# LoRa_Mini_Dev_v1_3.net
KiCad netlist of a schematic drawn in EAGLE
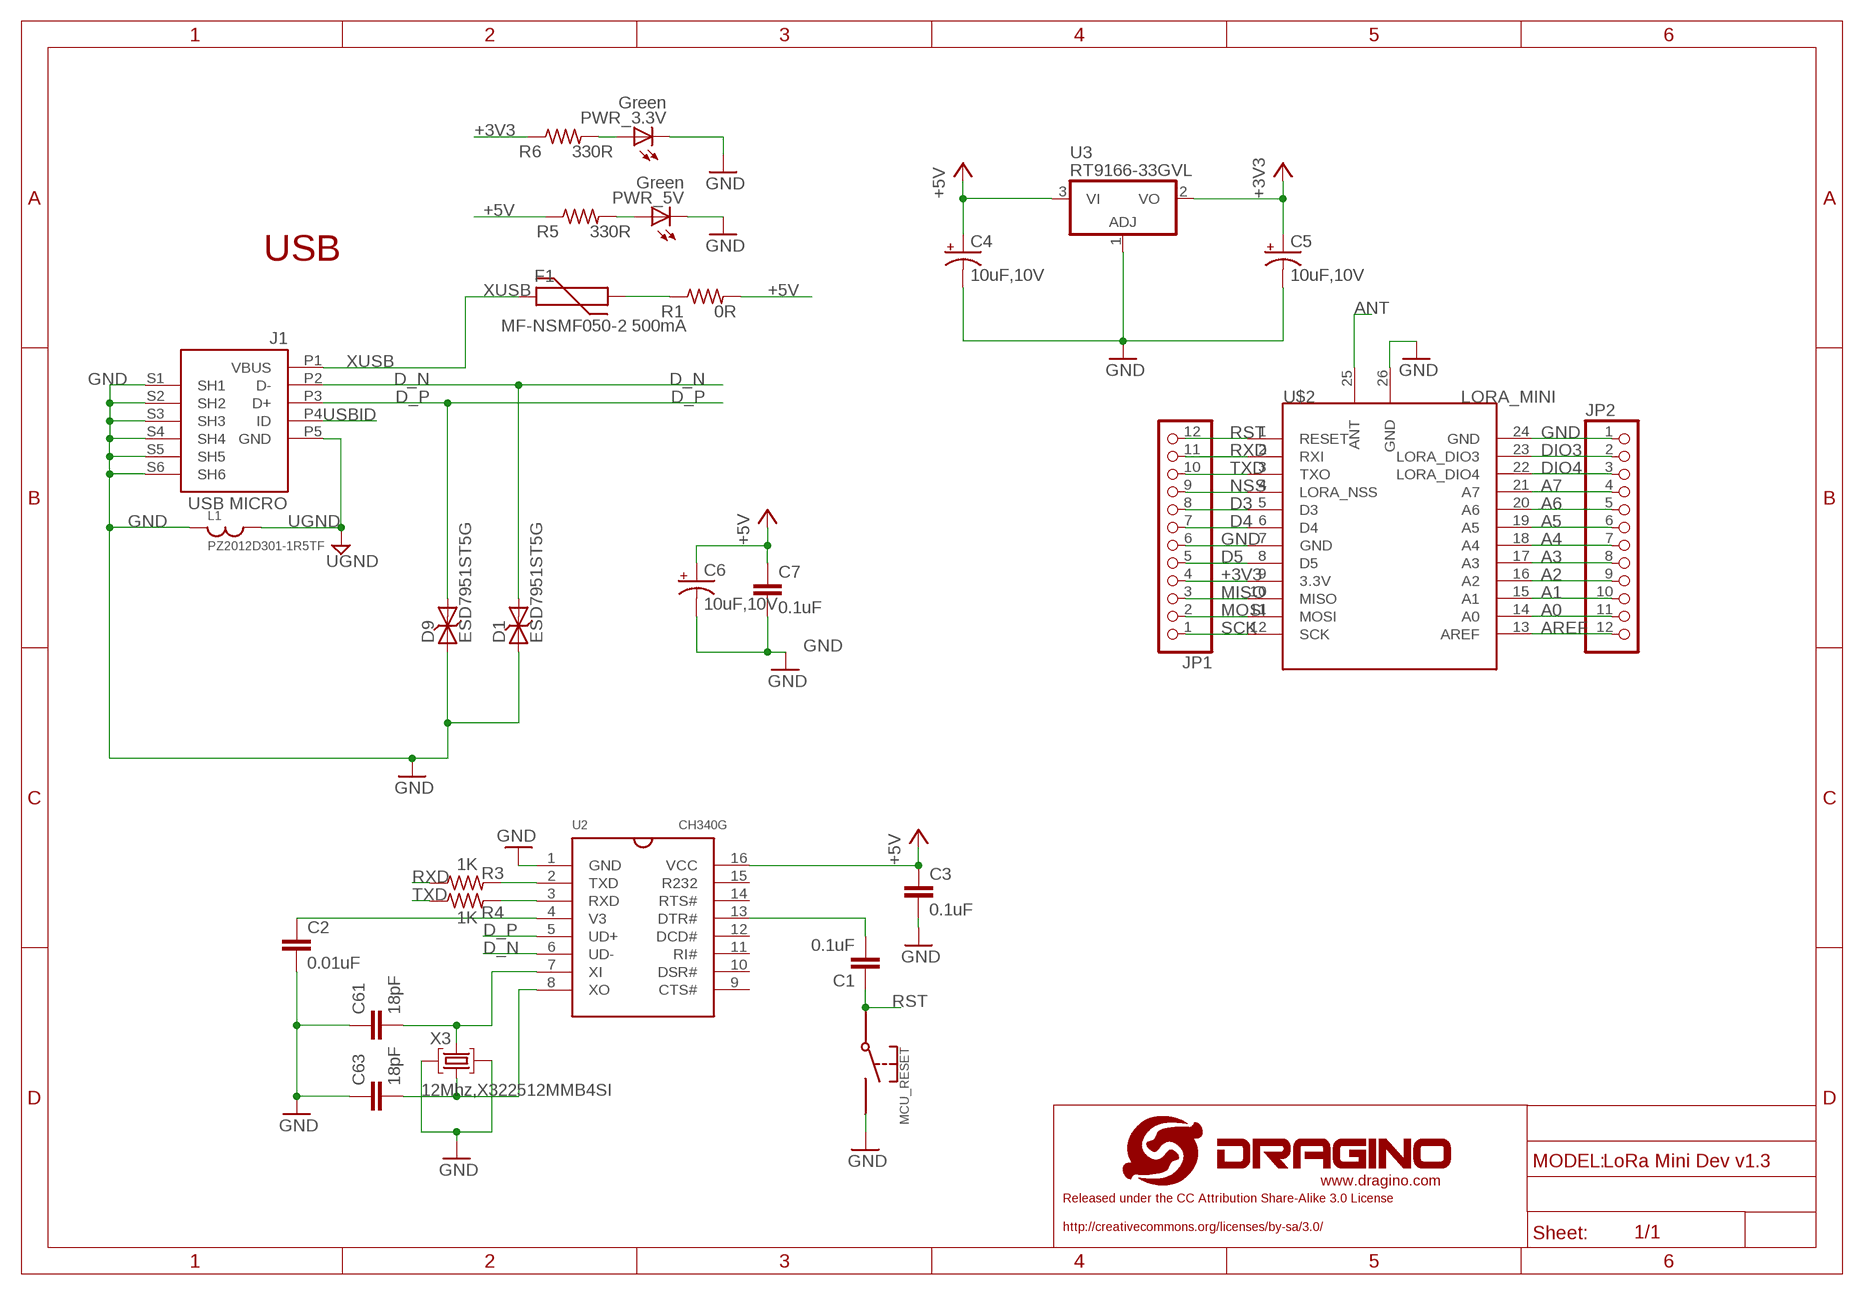
[diagram p0: schematic, sheet 1]

(export (version "E")
  (design (tool "Eeschema 10.0.6"))
  (components
    (comp (ref "C1")
      (value "0.1uF")
      (footprint "eagle-import:C0402")
      (libsource (lib "eagle-import") (part "C-EUC0402"))
    )
    (comp (ref "C2")
      (value "0.01uF")
      (footprint "eagle-import:C0402")
      (libsource (lib "eagle-import") (part "C-EUC0402"))
    )
    (comp (ref "C3")
      (value "0.1uF")
      (footprint "eagle-import:C0402")
      (libsource (lib "eagle-import") (part "C-EUC0402"))
    )
    (comp (ref "C4")
      (value "10uF,10V")
      (footprint "eagle-import:SMC_A")
      (libsource (lib "eagle-import") (part "CPOL-USSMCA"))
    )
    (comp (ref "C5")
      (value "10uF,10V")
      (footprint "eagle-import:SMC_A")
      (libsource (lib "eagle-import") (part "CPOL-USSMCA"))
    )
    (comp (ref "C6")
      (value "10uF,10V")
      (footprint "eagle-import:SMC_A")
      (libsource (lib "eagle-import") (part "CPOL-USSMCA"))
    )
    (comp (ref "C7")
      (value "0.1uF")
      (footprint "eagle-import:C0402")
      (libsource (lib "eagle-import") (part "C-EUC0402"))
    )
    (comp (ref "C61")
      (value "18pF")
      (footprint "eagle-import:C0402")
      (libsource (lib "eagle-import") (part "C-EUC0402"))
    )
    (comp (ref "C63")
      (value "18pF")
      (footprint "eagle-import:C0402")
      (libsource (lib "eagle-import") (part "C-EUC0402"))
    )
    (comp (ref "D1")
      (value "ESD7951ST5G")
      (footprint "eagle-import:SOD−923")
      (libsource (lib "eagle-import") (part "TVSSOD−923"))
    )
    (comp (ref "D9")
      (value "ESD7951ST5G")
      (footprint "eagle-import:SOD−923")
      (libsource (lib "eagle-import") (part "TVSSOD−923"))
    )
    (comp (ref "F1")
      (value "MF-NSMF050-2 500mA")
      (footprint "eagle-import:R1206")
      (libsource (lib "eagle-import") (part "FUSE1206"))
    )
    (comp (ref "J1")
      (value "USB MICRO")
      (footprint "eagle-import:CON2_USB_MICRO_B_AT")
      (libsource (lib "eagle-import") (part "MYCON2_USB-MINI-B"))
    )
    (comp (ref "JP1")
      (value "PINHD-1X12")
      (footprint "eagle-import:1X12")
      (libsource (lib "eagle-import") (part "PINHD-1X12"))
    )
    (comp (ref "JP2")
      (value "PINHD-1X12")
      (footprint "eagle-import:1X12")
      (libsource (lib "eagle-import") (part "PINHD-1X12"))
    )
    (comp (ref "L1")
      (value "PZ2012D301-1R5TF")
      (footprint "eagle-import:C0805")
      (libsource (lib "eagle-import") (part "BEADS0805"))
    )
    (comp (ref "MCU_RESET")
      (value "SWITCH")
      (footprint "eagle-import:SWITCH_3X6X5MM")
      (libsource (lib "eagle-import") (part "SWITCH"))
    )
    (comp (ref "PWR_3.3V")
      (value "Green")
      (footprint "eagle-import:DRAGINO_CHIPLED_0603")
      (libsource (lib "eagle-import") (part "DRAGINO_LEDCHIPLED_0603"))
    )
    (comp (ref "PWR_5V")
      (value "Green")
      (footprint "eagle-import:DRAGINO_CHIPLED_0603")
      (libsource (lib "eagle-import") (part "DRAGINO_LEDCHIPLED_0603"))
    )
    (comp (ref "R1")
      (value "0R")
      (footprint "eagle-import:R0805")
      (libsource (lib "eagle-import") (part "R-US_R0805"))
    )
    (comp (ref "R3")
      (value "1K")
      (footprint "eagle-import:R0402")
      (libsource (lib "eagle-import") (part "R-US_R0402"))
    )
    (comp (ref "R4")
      (value "1K")
      (footprint "eagle-import:R0402")
      (libsource (lib "eagle-import") (part "R-US_R0402"))
    )
    (comp (ref "R5")
      (value "330R")
      (footprint "eagle-import:R0402")
      (libsource (lib "eagle-import") (part "R-US_R0402"))
    )
    (comp (ref "R6")
      (value "330R")
      (footprint "eagle-import:R0402")
      (libsource (lib "eagle-import") (part "R-US_R0402"))
    )
    (comp (ref "U$1")
      (value "LOGO-NEW")
      (footprint "eagle-import:LOGO-SILK-NEW")
      (libsource (lib "eagle-import") (part "LOGO-NEW"))
    )
    (comp (ref "U$2")
      (value "LORA_MINI")
      (footprint "eagle-import:LORA_MINI_PCB")
      (libsource (lib "eagle-import") (part "LORA_MINIB"))
    )
    (comp (ref "U2")
      (value "CH340G")
      (footprint "eagle-import:CH340G")
      (libsource (lib "eagle-import") (part "CH340G"))
    )
    (comp (ref "U3")
      (value "RT9166-33GVL")
      (footprint "eagle-import:SOT23")
      (libsource (lib "eagle-import") (part "RT9166/A"))
    )
    (comp (ref "X3")
      (value "12Mhz,X322512MMB4SI")
      (footprint "eagle-import:SMARTPRJ_CRYSTAL-3.2-2.5")
      (libsource (lib "eagle-import") (part "CRYSTAL"))
    )
  )
  (nets
    (net (code "1") (name "+3V3") (class "Default")
      (node (ref "C5") (pin "+") (pinfunction "+_+") (pintype "passive"))
      (node (ref "JP1") (pin "4") (pinfunction "4_4") (pintype "passive"))
      (node (ref "R6") (pin "1") (pinfunction "1_1") (pintype "passive"))
      (node (ref "U$2") (pin "9") (pinfunction "3.3V_9") (pintype "bidirectional"))
      (node (ref "U3") (pin "2") (pinfunction "VO_2") (pintype "passive"))
    )
    (net (code "2") (name "+5V") (class "Default")
      (node (ref "C3") (pin "1") (pinfunction "1_1") (pintype "passive"))
      (node (ref "C4") (pin "+") (pinfunction "+_+") (pintype "passive"))
      (node (ref "C6") (pin "+") (pinfunction "+_+") (pintype "passive"))
      (node (ref "C7") (pin "1") (pinfunction "1_1") (pintype "passive"))
      (node (ref "R1") (pin "2") (pinfunction "2_2") (pintype "passive"))
      (node (ref "R5") (pin "1") (pinfunction "1_1") (pintype "passive"))
      (node (ref "U2") (pin "16") (pinfunction "VCC_16") (pintype "bidirectional"))
      (node (ref "U3") (pin "3") (pinfunction "VI_3") (pintype "input"))
    )
    (net (code "3") (name "/A0") (class "Default")
      (node (ref "JP2") (pin "11") (pinfunction "11_11") (pintype "passive"))
      (node (ref "U$2") (pin "14") (pinfunction "A0_14") (pintype "bidirectional"))
    )
    (net (code "4") (name "/A1") (class "Default")
      (node (ref "JP2") (pin "10") (pinfunction "10_10") (pintype "passive"))
      (node (ref "U$2") (pin "15") (pinfunction "A1_15") (pintype "bidirectional"))
    )
    (net (code "5") (name "/A2") (class "Default")
      (node (ref "JP2") (pin "9") (pinfunction "9_9") (pintype "passive"))
      (node (ref "U$2") (pin "16") (pinfunction "A2_16") (pintype "bidirectional"))
    )
    (net (code "6") (name "/A3") (class "Default")
      (node (ref "JP2") (pin "8") (pinfunction "8_8") (pintype "passive"))
      (node (ref "U$2") (pin "17") (pinfunction "A3_17") (pintype "bidirectional"))
    )
    (net (code "7") (name "/A4") (class "Default")
      (node (ref "JP2") (pin "7") (pinfunction "7_7") (pintype "passive"))
      (node (ref "U$2") (pin "18") (pinfunction "A4_18") (pintype "bidirectional"))
    )
    (net (code "8") (name "/A5") (class "Default")
      (node (ref "JP2") (pin "6") (pinfunction "6_6") (pintype "passive"))
      (node (ref "U$2") (pin "19") (pinfunction "A5_19") (pintype "bidirectional"))
    )
    (net (code "9") (name "/A6") (class "Default")
      (node (ref "JP2") (pin "5") (pinfunction "5_5") (pintype "passive"))
      (node (ref "U$2") (pin "20") (pinfunction "A6_20") (pintype "bidirectional"))
    )
    (net (code "10") (name "/A7") (class "Default")
      (node (ref "JP2") (pin "4") (pinfunction "4_4") (pintype "passive"))
      (node (ref "U$2") (pin "21") (pinfunction "A7_21") (pintype "bidirectional"))
    )
    (net (code "11") (name "/ANT") (class "Default")
      (node (ref "U$2") (pin "25") (pinfunction "ANT_25") (pintype "bidirectional"))
    )
    (net (code "12") (name "/AREF") (class "Default")
      (node (ref "JP2") (pin "12") (pinfunction "12_12") (pintype "passive"))
      (node (ref "U$2") (pin "13") (pinfunction "AREF_13") (pintype "bidirectional"))
    )
    (net (code "13") (name "/D3") (class "Default")
      (node (ref "JP1") (pin "8") (pinfunction "8_8") (pintype "passive"))
      (node (ref "U$2") (pin "5") (pinfunction "D3_5") (pintype "bidirectional"))
    )
    (net (code "14") (name "/D4") (class "Default")
      (node (ref "JP1") (pin "7") (pinfunction "7_7") (pintype "passive"))
      (node (ref "U$2") (pin "6") (pinfunction "D4_6") (pintype "bidirectional"))
    )
    (net (code "15") (name "/D5") (class "Default")
      (node (ref "JP1") (pin "5") (pinfunction "5_5") (pintype "passive"))
      (node (ref "U$2") (pin "8") (pinfunction "D5_8") (pintype "bidirectional"))
    )
    (net (code "16") (name "/DIO3") (class "Default")
      (node (ref "JP2") (pin "2") (pinfunction "2_2") (pintype "passive"))
      (node (ref "U$2") (pin "23") (pinfunction "LORA_DIO3_23") (pintype "bidirectional"))
    )
    (net (code "17") (name "/DIO4") (class "Default")
      (node (ref "JP2") (pin "3") (pinfunction "3_3") (pintype "passive"))
      (node (ref "U$2") (pin "22") (pinfunction "LORA_DIO4_22") (pintype "bidirectional"))
    )
    (net (code "18") (name "/D_N") (class "Default")
      (node (ref "D1") (pin "P$2") (pinfunction "2_P$2") (pintype "passive"))
      (node (ref "J1") (pin "P2") (pinfunction "D-_P2") (pintype "bidirectional"))
      (node (ref "U2") (pin "6") (pinfunction "UD-_6") (pintype "bidirectional"))
    )
    (net (code "19") (name "/D_P") (class "Default")
      (node (ref "D9") (pin "P$2") (pinfunction "2_P$2") (pintype "passive"))
      (node (ref "J1") (pin "P3") (pinfunction "D+_P3") (pintype "bidirectional"))
      (node (ref "U2") (pin "5") (pinfunction "UD+_5") (pintype "bidirectional"))
    )
    (net (code "20") (name "/MISO") (class "Default")
      (node (ref "JP1") (pin "3") (pinfunction "3_3") (pintype "passive"))
      (node (ref "U$2") (pin "10") (pinfunction "MISO_10") (pintype "bidirectional"))
    )
    (net (code "21") (name "/MOSI") (class "Default")
      (node (ref "JP1") (pin "2") (pinfunction "2_2") (pintype "passive"))
      (node (ref "U$2") (pin "11") (pinfunction "MOSI_11") (pintype "bidirectional"))
    )
    (net (code "22") (name "/NSS") (class "Default")
      (node (ref "JP1") (pin "9") (pinfunction "9_9") (pintype "passive"))
      (node (ref "U$2") (pin "4") (pinfunction "LORA_NSS_4") (pintype "bidirectional"))
    )
    (net (code "23") (name "/RST") (class "Default")
      (node (ref "C1") (pin "1") (pinfunction "1_1") (pintype "passive"))
      (node (ref "JP1") (pin "12") (pinfunction "12_12") (pintype "passive"))
      (node (ref "MCU_RESET") (pin "P$1") (pinfunction "P$1_P$1") (pintype "bidirectional"))
      (node (ref "U$2") (pin "1") (pinfunction "RESET_1") (pintype "bidirectional"))
    )
    (net (code "24") (name "/RXD") (class "Default")
      (node (ref "JP1") (pin "11") (pinfunction "11_11") (pintype "passive"))
      (node (ref "R3") (pin "1") (pinfunction "1_1") (pintype "passive"))
      (node (ref "U$2") (pin "2") (pinfunction "RXI_2") (pintype "bidirectional"))
    )
    (net (code "25") (name "/SCK") (class "Default")
      (node (ref "JP1") (pin "1") (pinfunction "1_1") (pintype "passive"))
      (node (ref "U$2") (pin "12") (pinfunction "SCK_12") (pintype "bidirectional"))
    )
    (net (code "26") (name "/TXD") (class "Default")
      (node (ref "JP1") (pin "10") (pinfunction "10_10") (pintype "passive"))
      (node (ref "R4") (pin "1") (pinfunction "1_1") (pintype "passive"))
      (node (ref "U$2") (pin "3") (pinfunction "TXO_3") (pintype "bidirectional"))
    )
    (net (code "27") (name "/USBID") (class "Default")
      (node (ref "J1") (pin "P4") (pinfunction "ID_P4") (pintype "bidirectional"))
    )
    (net (code "28") (name "/XUSB") (class "Default")
      (node (ref "F1") (pin "2") (pinfunction "2_2") (pintype "passive"))
      (node (ref "J1") (pin "P1") (pinfunction "VBUS_P1") (pintype "power_in"))
    )
    (net (code "29") (name "GND") (class "Default")
      (node (ref "C2") (pin "2") (pinfunction "2_2") (pintype "passive"))
      (node (ref "C3") (pin "2") (pinfunction "2_2") (pintype "passive"))
      (node (ref "C4") (pin "-") (pinfunction "-_-") (pintype "passive"))
      (node (ref "C5") (pin "-") (pinfunction "-_-") (pintype "passive"))
      (node (ref "C6") (pin "-") (pinfunction "-_-") (pintype "passive"))
      (node (ref "C61") (pin "1") (pinfunction "1_1") (pintype "passive"))
      (node (ref "C63") (pin "1") (pinfunction "1_1") (pintype "passive"))
      (node (ref "C7") (pin "2") (pinfunction "2_2") (pintype "passive"))
      (node (ref "D1") (pin "P$1") (pinfunction "1_P$1") (pintype "passive"))
      (node (ref "D9") (pin "P$1") (pinfunction "1_P$1") (pintype "passive"))
      (node (ref "J1") (pin "S1") (pinfunction "SH1_S1") (pintype "passive"))
      (node (ref "J1") (pin "S2") (pinfunction "SH2_S2") (pintype "passive"))
      (node (ref "J1") (pin "S3") (pinfunction "SH3_S3") (pintype "passive"))
      (node (ref "J1") (pin "S4") (pinfunction "SH4_S4") (pintype "passive"))
      (node (ref "J1") (pin "S5") (pinfunction "SH5_S5") (pintype "passive"))
      (node (ref "J1") (pin "S6") (pinfunction "SH6_S6") (pintype "passive"))
      (node (ref "JP1") (pin "6") (pinfunction "6_6") (pintype "passive"))
      (node (ref "JP2") (pin "1") (pinfunction "1_1") (pintype "passive"))
      (node (ref "L1") (pin "1") (pinfunction "P$1_1") (pintype "bidirectional"))
      (node (ref "MCU_RESET") (pin "P$2") (pinfunction "P$2_P$2") (pintype "bidirectional"))
      (node (ref "PWR_3.3V") (pin "C") (pinfunction "C_C") (pintype "passive"))
      (node (ref "PWR_5V") (pin "C") (pinfunction "C_C") (pintype "passive"))
      (node (ref "U$2") (pin "24") (pinfunction "GND_24") (pintype "bidirectional"))
      (node (ref "U$2") (pin "26") (pinfunction "GND_26") (pintype "bidirectional"))
      (node (ref "U$2") (pin "7") (pinfunction "GND_7") (pintype "bidirectional"))
      (node (ref "U2") (pin "1") (pinfunction "GND_1") (pintype "bidirectional"))
      (node (ref "U3") (pin "1") (pinfunction "ADJ_1") (pintype "input"))
      (node (ref "X3") (pin "2") (pinfunction "GND_2") (pintype "passive"))
      (node (ref "X3") (pin "4") (pinfunction "GND_4") (pintype "passive"))
    )
    (net (code "30") (name "Net-(F1-Pad1)") (class "Default")
      (node (ref "F1") (pin "1") (pinfunction "1_1") (pintype "passive"))
      (node (ref "R1") (pin "1") (pinfunction "1_1") (pintype "passive"))
    )
    (net (code "31") (name "Net-(PWR_3.3V-PadA)") (class "Default")
      (node (ref "PWR_3.3V") (pin "A") (pinfunction "A_A") (pintype "passive"))
      (node (ref "R6") (pin "2") (pinfunction "2_2") (pintype "passive"))
    )
    (net (code "32") (name "Net-(PWR_5V-PadA)") (class "Default")
      (node (ref "PWR_5V") (pin "A") (pinfunction "A_A") (pintype "passive"))
      (node (ref "R5") (pin "2") (pinfunction "2_2") (pintype "passive"))
    )
    (net (code "33") (name "Net-(U2-DTR#)") (class "Default")
      (node (ref "C1") (pin "2") (pinfunction "2_2") (pintype "passive"))
      (node (ref "U2") (pin "13") (pinfunction "DTR#_13") (pintype "bidirectional"))
    )
    (net (code "34") (name "Net-(U2-RXD)") (class "Default")
      (node (ref "R4") (pin "2") (pinfunction "2_2") (pintype "passive"))
      (node (ref "U2") (pin "3") (pinfunction "RXD_3") (pintype "bidirectional"))
    )
    (net (code "35") (name "Net-(U2-TXD)") (class "Default")
      (node (ref "R3") (pin "2") (pinfunction "2_2") (pintype "passive"))
      (node (ref "U2") (pin "2") (pinfunction "TXD_2") (pintype "bidirectional"))
    )
    (net (code "36") (name "Net-(U2-V3)") (class "Default")
      (node (ref "C2") (pin "1") (pinfunction "1_1") (pintype "passive"))
      (node (ref "U2") (pin "4") (pinfunction "V3_4") (pintype "bidirectional"))
    )
    (net (code "37") (name "Net-(U2-XI)") (class "Default")
      (node (ref "C61") (pin "2") (pinfunction "2_2") (pintype "passive"))
      (node (ref "U2") (pin "7") (pinfunction "XI_7") (pintype "bidirectional"))
      (node (ref "X3") (pin "3") (pinfunction "C2_3") (pintype "passive"))
    )
    (net (code "38") (name "Net-(U2-XO)") (class "Default")
      (node (ref "C63") (pin "2") (pinfunction "2_2") (pintype "passive"))
      (node (ref "U2") (pin "8") (pinfunction "XO_8") (pintype "bidirectional"))
      (node (ref "X3") (pin "1") (pinfunction "C1_1") (pintype "passive"))
    )
    (net (code "39") (name "UGND") (class "Default")
      (node (ref "J1") (pin "P5") (pinfunction "GND_P5") (pintype "passive"))
      (node (ref "L1") (pin "2") (pinfunction "P$2_2") (pintype "bidirectional"))
    )
    (net (code "40") (name "unconnected-(U2-CTS#-Pad9)") (class "Default")
      (node (ref "U2") (pin "9") (pinfunction "CTS#_9") (pintype "bidirectional"))
    )
    (net (code "41") (name "unconnected-(U2-DCD#-Pad12)") (class "Default")
      (node (ref "U2") (pin "12") (pinfunction "DCD#_12") (pintype "bidirectional"))
    )
    (net (code "42") (name "unconnected-(U2-DSR#-Pad10)") (class "Default")
      (node (ref "U2") (pin "10") (pinfunction "DSR#_10") (pintype "bidirectional"))
    )
    (net (code "43") (name "unconnected-(U2-R232-Pad15)") (class "Default")
      (node (ref "U2") (pin "15") (pinfunction "R232_15") (pintype "bidirectional"))
    )
    (net (code "44") (name "unconnected-(U2-RI#-Pad11)") (class "Default")
      (node (ref "U2") (pin "11") (pinfunction "RI#_11") (pintype "bidirectional"))
    )
    (net (code "45") (name "unconnected-(U2-RTS#-Pad14)") (class "Default")
      (node (ref "U2") (pin "14") (pinfunction "RTS#_14") (pintype "bidirectional"))
    )
  )
)
